# HBridge.net
KiCad netlist of a schematic drawn in Altium Designer
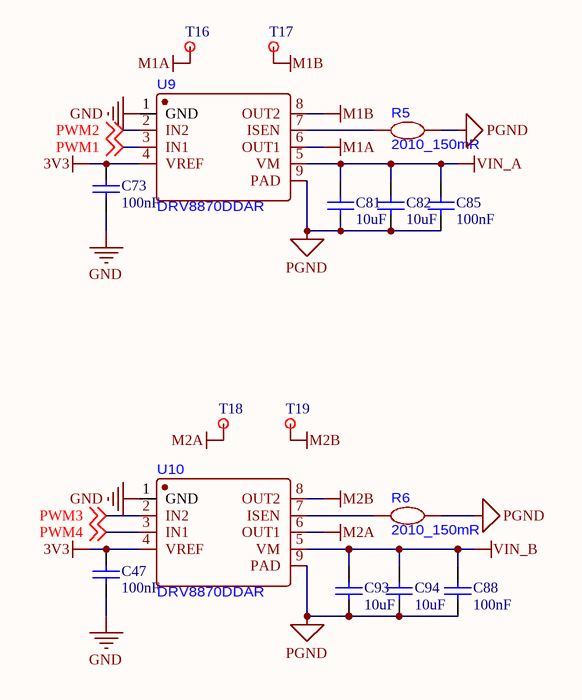
[diagram p0: HBridge.SchDoc]

(export (version "E")
  (design (tool "Eeschema 10.0.6"))
  (components
    (comp (ref "C47")
      (value "100nF")
      (footprint "0402_C")
      (description "贴片电容")
      (libsource (lib "Miscellaneous Devices LC") (part "0402 100nF (104) 10% 16V"))
    )
    (comp (ref "C73")
      (value "100nF")
      (footprint "0402_C")
      (description "贴片电容")
      (libsource (lib "Miscellaneous Devices LC") (part "0402 100nF (104) 10% 16V"))
    )
    (comp (ref "C81")
      (value "10uF")
      (footprint "1206_C")
      (description "贴片电容")
      (libsource (lib "Miscellaneous Devices LC") (part "1206 10uF (106) 10% 50V"))
    )
    (comp (ref "C82")
      (value "10uF")
      (footprint "1206_C")
      (description "贴片电容")
      (libsource (lib "Miscellaneous Devices LC") (part "1206 10uF (106) 10% 50V"))
    )
    (comp (ref "C85")
      (value "100nF")
      (footprint "0402_C")
      (description "贴片电容")
      (libsource (lib "Miscellaneous Devices LC") (part "0402 100nF (104) 10% 16V"))
    )
    (comp (ref "C88")
      (value "100nF")
      (footprint "0402_C")
      (description "贴片电容")
      (libsource (lib "Miscellaneous Devices LC") (part "0402 100nF (104) 10% 16V"))
    )
    (comp (ref "C93")
      (value "10uF")
      (footprint "1206_C")
      (description "贴片电容")
      (libsource (lib "Miscellaneous Devices LC") (part "1206 10uF (106) 10% 50V"))
    )
    (comp (ref "C94")
      (value "10uF")
      (footprint "1206_C")
      (description "贴片电容")
      (libsource (lib "Miscellaneous Devices LC") (part "1206 10uF (106) 10% 50V"))
    )
    (comp (ref "R5") (value "2010_150mR") (footprint "R2010") (libsource (lib "JiangCi") (part "2010_150mR")))
    (comp (ref "R6") (value "2010_150mR") (footprint "R2010") (libsource (lib "JiangCi") (part "2010_150mR")))
    (comp (ref "T16")
      (value "testpoint")
      (footprint "testpoint")
      (libsource (lib "JiangCi") (part "testpoint"))
    )
    (comp (ref "T17")
      (value "testpoint")
      (footprint "testpoint")
      (libsource (lib "JiangCi") (part "testpoint"))
    )
    (comp (ref "T18")
      (value "testpoint")
      (footprint "testpoint")
      (libsource (lib "JiangCi") (part "testpoint"))
    )
    (comp (ref "T19")
      (value "testpoint")
      (footprint "testpoint")
      (libsource (lib "JiangCi") (part "testpoint"))
    )
    (comp (ref "U9")
      (value "DRV8870DDAR")
      (footprint "HSOP-8_L5.0-W4.0-P1.27-LS6.2-BL-EP")
      (libsource (lib "JiangCi") (part "DRV8870DDAR"))
    )
    (comp (ref "U10")
      (value "DRV8870DDAR")
      (footprint "HSOP-8_L5.0-W4.0-P1.27-LS6.2-BL-EP")
      (libsource (lib "JiangCi") (part "DRV8870DDAR"))
    )
  )
  (nets
    (net (code "1") (name "3V3") (class "Default")
      (node (ref "C47") (pin "2") (pinfunction "2_2") (pintype "passive"))
      (node (ref "C73") (pin "2") (pinfunction "2_2") (pintype "passive"))
      (node (ref "U10") (pin "4") (pinfunction "VREF_4") (pintype "passive"))
      (node (ref "U9") (pin "4") (pinfunction "VREF_4") (pintype "passive"))
    )
    (net (code "2") (name "GND") (class "Default")
      (node (ref "C47") (pin "1") (pinfunction "1_1") (pintype "passive"))
      (node (ref "C73") (pin "1") (pinfunction "1_1") (pintype "passive"))
      (node (ref "U10") (pin "1") (pinfunction "GND_1") (pintype "passive"))
      (node (ref "U9") (pin "1") (pinfunction "GND_1") (pintype "passive"))
    )
    (net (code "3") (name "M1A") (class "Default")
      (node (ref "T16") (pin "1") (pinfunction "R_1") (pintype "passive"))
      (node (ref "U9") (pin "6") (pinfunction "OUT1_6") (pintype "passive"))
    )
    (net (code "4") (name "M1B") (class "Default")
      (node (ref "T17") (pin "1") (pinfunction "R_1") (pintype "passive"))
      (node (ref "U9") (pin "8") (pinfunction "OUT2_8") (pintype "passive"))
    )
    (net (code "5") (name "M2A") (class "Default")
      (node (ref "T18") (pin "1") (pinfunction "R_1") (pintype "passive"))
      (node (ref "U10") (pin "6") (pinfunction "OUT1_6") (pintype "passive"))
    )
    (net (code "6") (name "M2B") (class "Default")
      (node (ref "T19") (pin "1") (pinfunction "R_1") (pintype "passive"))
      (node (ref "U10") (pin "8") (pinfunction "OUT2_8") (pintype "passive"))
    )
    (net (code "7") (name "Net-(U9-ISEN)") (class "Default")
      (node (ref "R5") (pin "1") (pinfunction "1_1") (pintype "passive"))
      (node (ref "U9") (pin "7") (pinfunction "ISEN_7") (pintype "passive"))
    )
    (net (code "8") (name "Net-(U10-ISEN)") (class "Default")
      (node (ref "R6") (pin "1") (pinfunction "1_1") (pintype "passive"))
      (node (ref "U10") (pin "7") (pinfunction "ISEN_7") (pintype "passive"))
    )
    (net (code "9") (name "PGND") (class "Default")
      (node (ref "C81") (pin "1") (pinfunction "1_1") (pintype "passive"))
      (node (ref "C82") (pin "1") (pinfunction "1_1") (pintype "passive"))
      (node (ref "C85") (pin "1") (pinfunction "1_1") (pintype "passive"))
      (node (ref "C88") (pin "1") (pinfunction "1_1") (pintype "passive"))
      (node (ref "C93") (pin "1") (pinfunction "1_1") (pintype "passive"))
      (node (ref "C94") (pin "1") (pinfunction "1_1") (pintype "passive"))
      (node (ref "R5") (pin "2") (pinfunction "2_2") (pintype "passive"))
      (node (ref "R6") (pin "2") (pinfunction "2_2") (pintype "passive"))
      (node (ref "U10") (pin "9") (pinfunction "PAD_9") (pintype "passive"))
      (node (ref "U9") (pin "9") (pinfunction "PAD_9") (pintype "passive"))
    )
    (net (code "10") (name "PWM1") (class "Default")
      (node (ref "U9") (pin "3") (pinfunction "IN1_3") (pintype "passive"))
    )
    (net (code "11") (name "PWM2") (class "Default")
      (node (ref "U9") (pin "2") (pinfunction "IN2_2") (pintype "passive"))
    )
    (net (code "12") (name "PWM3") (class "Default")
      (node (ref "U10") (pin "2") (pinfunction "IN2_2") (pintype "passive"))
    )
    (net (code "13") (name "PWM4") (class "Default")
      (node (ref "U10") (pin "3") (pinfunction "IN1_3") (pintype "passive"))
    )
    (net (code "14") (name "VIN_A") (class "Default")
      (node (ref "C81") (pin "2") (pinfunction "2_2") (pintype "passive"))
      (node (ref "C82") (pin "2") (pinfunction "2_2") (pintype "passive"))
      (node (ref "C85") (pin "2") (pinfunction "2_2") (pintype "passive"))
      (node (ref "U9") (pin "5") (pinfunction "VM_5") (pintype "passive"))
    )
    (net (code "15") (name "VIN_B") (class "Default")
      (node (ref "C88") (pin "2") (pinfunction "2_2") (pintype "passive"))
      (node (ref "C93") (pin "2") (pinfunction "2_2") (pintype "passive"))
      (node (ref "C94") (pin "2") (pinfunction "2_2") (pintype "passive"))
      (node (ref "U10") (pin "5") (pinfunction "VM_5") (pintype "passive"))
    )
  )
)
